# Sheet1.net
KiCad netlist of a schematic drawn in Altium Designer
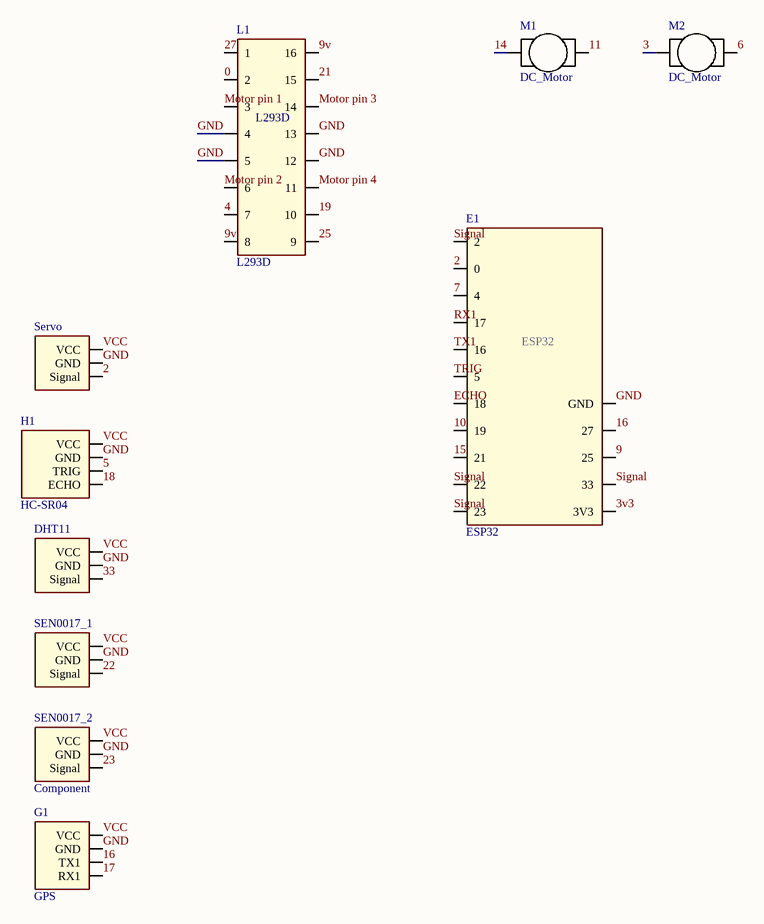
[diagram p0: Sheet1.SchDoc]

(export (version "E")
  (design (tool "Eeschema 10.0.6"))
  (components
    (comp (ref "DHT11") (value "Component") (libsource (lib "Schlib1") (part "Component")))
    (comp (ref "E1") (value "ESP32") (libsource (lib "Schlib1") (part "ESP32")))
    (comp (ref "G1") (value "GPS") (libsource (lib "Schlib1") (part "GPS")))
    (comp (ref "H1") (value "HC-SR04") (libsource (lib "Schlib1") (part "HC-SR04")))
    (comp (ref "L1") (value "L293D") (libsource (lib "Schlib1") (part "L293D")))
    (comp (ref "M1") (value "DC_Motor") (libsource (lib "Schlib1") (part "DC_Motor")))
    (comp (ref "M2") (value "DC_Motor") (libsource (lib "Schlib1") (part "DC_Motor")))
    (comp (ref "SEN0017_1") (value "Component") (libsource (lib "Schlib1") (part "Component")))
    (comp (ref "SEN0017_2") (value "Component") (libsource (lib "Schlib1") (part "Component")))
    (comp (ref "Servo") (value "Component") (libsource (lib "Schlib1") (part "Component")))
  )
  (nets
    (net (code "1") (name "/0") (class "Default")
      (node (ref "L1") (pin "2") (pinfunction "2_2") (pintype "passive"))
    )
    (net (code "2") (name "/2") (class "Default")
      (node (ref "E1") (pin "0") (pinfunction "0_0") (pintype "passive"))
      (node (ref "Servo") (pin "2") (pinfunction "Signal_2") (pintype "passive"))
    )
    (net (code "3") (name "/3") (class "Default")
      (node (ref "M2") (pin "1") (pinfunction "1_1") (pintype "passive"))
    )
    (net (code "4") (name "/3v3") (class "Default")
      (node (ref "E1") (pin "3V3") (pinfunction "3V3_3V3") (pintype "passive"))
    )
    (net (code "5") (name "/4") (class "Default")
      (node (ref "L1") (pin "7") (pinfunction "7_7") (pintype "passive"))
    )
    (net (code "6") (name "/5") (class "Default")
      (node (ref "H1") (pin "2") (pinfunction "TRIG_2") (pintype "passive"))
    )
    (net (code "7") (name "/6") (class "Default") (node (ref "M2") (pin "0") (pintype "passive")))
    (net (code "8") (name "/7") (class "Default")
      (node (ref "E1") (pin "4") (pinfunction "4_4") (pintype "passive"))
    )
    (net (code "9") (name "/9") (class "Default")
      (node (ref "E1") (pin "25") (pinfunction "25_25") (pintype "passive"))
    )
    (net (code "10") (name "/9v") (class "Default")
      (node (ref "L1") (pin "16") (pinfunction "16_16") (pintype "passive"))
      (node (ref "L1") (pin "8") (pinfunction "8_8") (pintype "passive"))
    )
    (net (code "11") (name "/10") (class "Default")
      (node (ref "E1") (pin "19") (pinfunction "19_19") (pintype "passive"))
    )
    (net (code "12") (name "/11") (class "Default") (node (ref "M1") (pin "0") (pintype "passive")))
    (net (code "13") (name "/14") (class "Default")
      (node (ref "M1") (pin "1") (pinfunction "1_1") (pintype "passive"))
    )
    (net (code "14") (name "/15") (class "Default")
      (node (ref "E1") (pin "21") (pinfunction "21_21") (pintype "passive"))
    )
    (net (code "15") (name "/16") (class "Default")
      (node (ref "E1") (pin "27") (pinfunction "27_27") (pintype "passive"))
      (node (ref "G1") (pin "2") (pinfunction "TX1_2") (pintype "passive"))
    )
    (net (code "16") (name "/17") (class "Default")
      (node (ref "G1") (pin "3") (pinfunction "RX1_3") (pintype "passive"))
    )
    (net (code "17") (name "/18") (class "Default")
      (node (ref "H1") (pin "3") (pinfunction "ECHO_3") (pintype "passive"))
    )
    (net (code "18") (name "/19") (class "Default")
      (node (ref "L1") (pin "10") (pinfunction "10_10") (pintype "passive"))
    )
    (net (code "19") (name "/21") (class "Default")
      (node (ref "L1") (pin "15") (pinfunction "15_15") (pintype "passive"))
    )
    (net (code "20") (name "/22") (class "Default")
      (node (ref "SEN0017_1") (pin "2") (pinfunction "Signal_2") (pintype "passive"))
    )
    (net (code "21") (name "/23") (class "Default")
      (node (ref "SEN0017_2") (pin "2") (pinfunction "Signal_2") (pintype "passive"))
    )
    (net (code "22") (name "/25") (class "Default")
      (node (ref "L1") (pin "9") (pinfunction "9_9") (pintype "passive"))
    )
    (net (code "23") (name "/27") (class "Default")
      (node (ref "L1") (pin "1") (pinfunction "1_1") (pintype "passive"))
    )
    (net (code "24") (name "/33") (class "Default")
      (node (ref "DHT11") (pin "2") (pinfunction "Signal_2") (pintype "passive"))
    )
    (net (code "25") (name "/ECHO") (class "Default")
      (node (ref "E1") (pin "18") (pinfunction "18_18") (pintype "passive"))
    )
    (net (code "26") (name "/GND") (class "Default")
      (node (ref "DHT11") (pin "1") (pinfunction "GND_1") (pintype "passive"))
      (node (ref "E1") (pin "GND") (pinfunction "GND_GND") (pintype "passive"))
      (node (ref "G1") (pin "1") (pinfunction "GND_1") (pintype "passive"))
      (node (ref "H1") (pin "1") (pinfunction "GND_1") (pintype "passive"))
      (node (ref "L1") (pin "12") (pinfunction "12_12") (pintype "passive"))
      (node (ref "L1") (pin "13") (pinfunction "13_13") (pintype "passive"))
      (node (ref "L1") (pin "4") (pinfunction "4_4") (pintype "passive"))
      (node (ref "L1") (pin "5") (pinfunction "5_5") (pintype "passive"))
      (node (ref "SEN0017_1") (pin "1") (pinfunction "GND_1") (pintype "passive"))
      (node (ref "SEN0017_2") (pin "1") (pinfunction "GND_1") (pintype "passive"))
      (node (ref "Servo") (pin "1") (pinfunction "GND_1") (pintype "passive"))
    )
    (net (code "27") (name "/Motor pin 1") (class "Default")
      (node (ref "L1") (pin "3") (pinfunction "3_3") (pintype "passive"))
    )
    (net (code "28") (name "/Motor pin 2") (class "Default")
      (node (ref "L1") (pin "6") (pinfunction "6_6") (pintype "passive"))
    )
    (net (code "29") (name "/Motor pin 3") (class "Default")
      (node (ref "L1") (pin "14") (pinfunction "14_14") (pintype "passive"))
    )
    (net (code "30") (name "/Motor pin 4") (class "Default")
      (node (ref "L1") (pin "11") (pinfunction "11_11") (pintype "passive"))
    )
    (net (code "31") (name "/RX1") (class "Default")
      (node (ref "E1") (pin "17") (pinfunction "17_17") (pintype "passive"))
    )
    (net (code "32") (name "/Signal") (class "Default")
      (node (ref "E1") (pin "2") (pinfunction "2_2") (pintype "passive"))
      (node (ref "E1") (pin "22") (pinfunction "22_22") (pintype "passive"))
      (node (ref "E1") (pin "23") (pinfunction "23_23") (pintype "passive"))
      (node (ref "E1") (pin "33") (pinfunction "33_33") (pintype "passive"))
    )
    (net (code "33") (name "/TRIG") (class "Default")
      (node (ref "E1") (pin "5") (pinfunction "5_5") (pintype "passive"))
    )
    (net (code "34") (name "/TX1") (class "Default")
      (node (ref "E1") (pin "16") (pinfunction "16_16") (pintype "passive"))
    )
    (net (code "35") (name "/VCC") (class "Default")
      (node (ref "DHT11") (pin "0") (pinfunction "VCC_0") (pintype "passive"))
      (node (ref "G1") (pin "0") (pinfunction "VCC_0") (pintype "passive"))
      (node (ref "H1") (pin "0") (pinfunction "VCC_0") (pintype "passive"))
      (node (ref "SEN0017_1") (pin "0") (pinfunction "VCC_0") (pintype "passive"))
      (node (ref "SEN0017_2") (pin "0") (pinfunction "VCC_0") (pintype "passive"))
      (node (ref "Servo") (pin "0") (pinfunction "VCC_0") (pintype "passive"))
    )
  )
)
